# CC2652P_STICK_v1_1.net
KiCad netlist of a schematic drawn in EAGLE
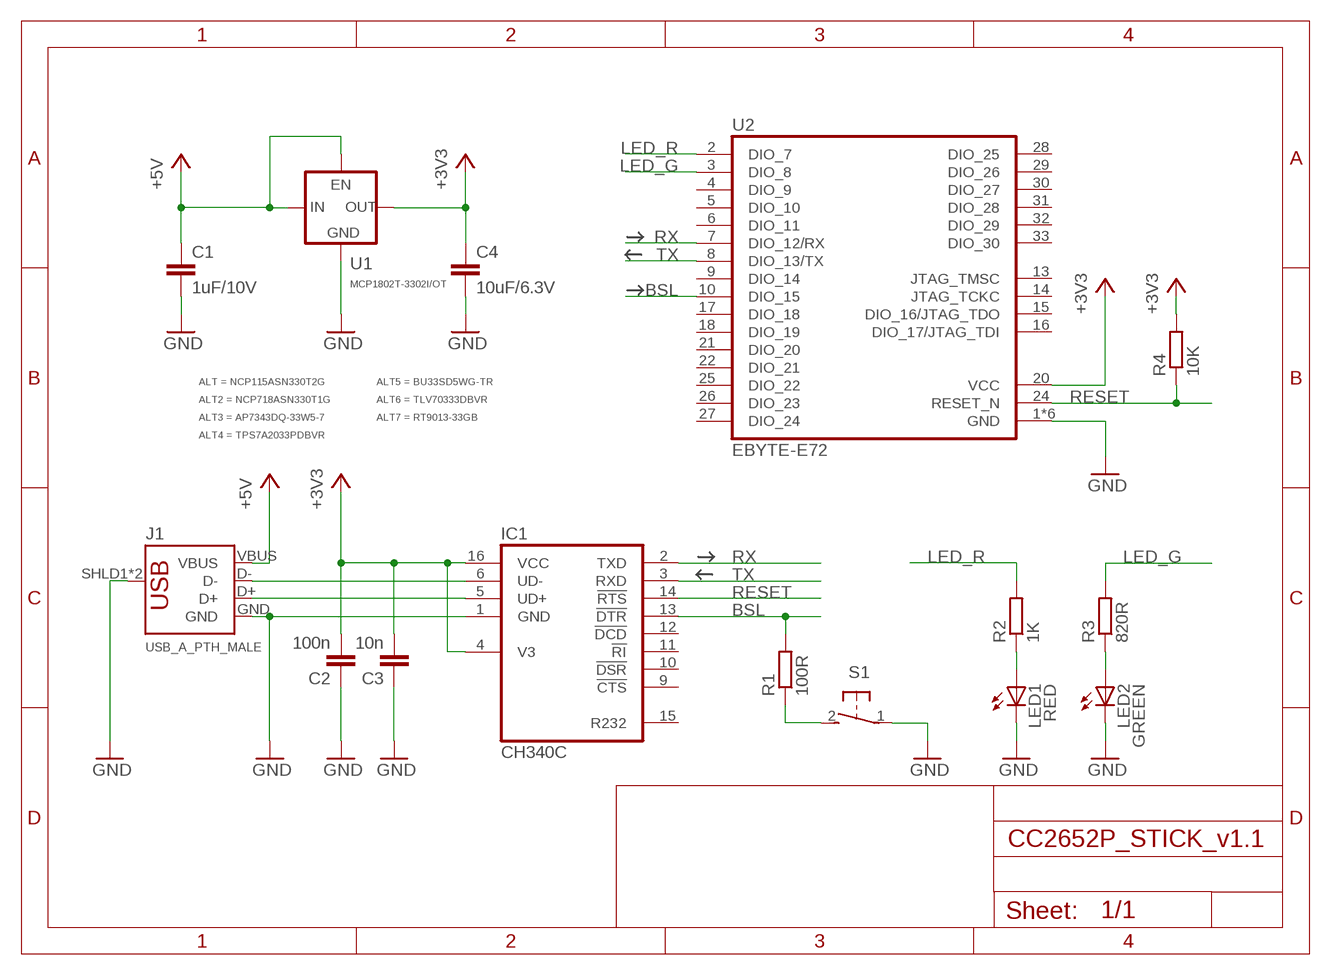
[diagram p0: schematic, sheet 1]

(export (version "E")
  (design (tool "Eeschema 10.0.6"))
  (components
    (comp (ref "C1")
      (value "1uF/10V")
      (footprint "eagle-import:C0805")
      (libsource (lib "eagle-import") (part "C-EUC0805"))
    )
    (comp (ref "C2")
      (value "100n")
      (footprint "eagle-import:C0805")
      (libsource (lib "eagle-import") (part "C-EUC0805"))
    )
    (comp (ref "C3")
      (value "10n")
      (footprint "eagle-import:C0805")
      (libsource (lib "eagle-import") (part "C-EUC0805"))
    )
    (comp (ref "C4")
      (value "10uF/6.3V")
      (footprint "eagle-import:C0805")
      (libsource (lib "eagle-import") (part "C-EUC0805"))
    )
    (comp (ref "IC1")
      (value "CH340C")
      (footprint "eagle-import:SO16")
      (libsource (lib "eagle-import") (part "CH340C"))
    )
    (comp (ref "J1")
      (value "USB_A_PTH_MALE")
      (footprint "eagle-import:USB-A-H")
      (libsource (lib "eagle-import") (part "USB_A_PTH_MALE"))
    )
    (comp (ref "LED1")
      (value "RED")
      (footprint "eagle-import:LED0603")
      (libsource (lib "eagle-import") (part "LED0603"))
    )
    (comp (ref "LED2")
      (value "GREEN")
      (footprint "eagle-import:LED0603")
      (libsource (lib "eagle-import") (part "LED0603"))
    )
    (comp (ref "R1")
      (value "100R")
      (footprint "eagle-import:R0805")
      (libsource (lib "eagle-import") (part "R-EU_R0805"))
    )
    (comp (ref "R2")
      (value "1K")
      (footprint "eagle-import:R0805")
      (libsource (lib "eagle-import") (part "R-EU_R0805"))
    )
    (comp (ref "R3")
      (value "820R")
      (footprint "eagle-import:R0805")
      (libsource (lib "eagle-import") (part "R-EU_R0805"))
    )
    (comp (ref "R4")
      (value "10K")
      (footprint "eagle-import:R0805")
      (libsource (lib "eagle-import") (part "R-EU_R0805"))
    )
    (comp (ref "S1")
      (value "DTSM-3")
      (footprint "eagle-import:DTSM-3")
      (libsource (lib "eagle-import") (part "DTSM-3"))
    )
    (comp (ref "U1")
      (value "MCP1802T-3302I/OT")
      (footprint "eagle-import:SOT23-5")
      (fields
        (field (name "ALT") "NCP115ASN330T2G")
        (field (name "ALT2") "NCP718ASN330T1G")
        (field (name "ALT3") "AP7343DQ-33W5-7")
        (field (name "ALT4") "TPS7A2033PDBVR")
        (field (name "ALT5") "BU33SD5WG-TR")
        (field (name "ALT6") "TLV70333DBVR")
        (field (name "ALT7") "RT9013-33GB")
      )
      (libsource (lib "eagle-import") (part "TLV700DD33"))
    )
    (comp (ref "U2")
      (value "EBYTE-E72")
      (footprint "eagle-import:EBYTE-E72")
      (libsource (lib "eagle-import") (part "EBYTE-E72"))
    )
  )
  (nets
    (net (code "1") (name "+3V3") (class "Default")
      (node (ref "C2") (pin "2") (pinfunction "2_2") (pintype "passive"))
      (node (ref "C3") (pin "2") (pinfunction "2_2") (pintype "passive"))
      (node (ref "C4") (pin "1") (pinfunction "1_1") (pintype "passive"))
      (node (ref "IC1") (pin "16") (pinfunction "VCC_16") (pintype "power_in"))
      (node (ref "IC1") (pin "4") (pinfunction "V3_4") (pintype "passive"))
      (node (ref "R4") (pin "2") (pinfunction "2_2") (pintype "passive"))
      (node (ref "U1") (pin "5") (pinfunction "VOUT_5") (pintype "power_in"))
      (node (ref "U2") (pin "20") (pinfunction "VCC_20") (pintype "power_in"))
    )
    (net (code "2") (name "+5V") (class "Default")
      (node (ref "C1") (pin "1") (pinfunction "1_1") (pintype "passive"))
      (node (ref "J1") (pin "VBUS") (pinfunction "VBUS_VBUS") (pintype "power_in"))
      (node (ref "U1") (pin "1") (pinfunction "VIN_1") (pintype "power_in"))
      (node (ref "U1") (pin "3") (pinfunction "EN_3") (pintype "input"))
    )
    (net (code "3") (name "/BSL") (class "Default")
      (node (ref "IC1") (pin "13") (pinfunction "~{DTR}_13") (pintype "bidirectional"))
      (node (ref "R1") (pin "2") (pinfunction "2_2") (pintype "passive"))
      (node (ref "U2") (pin "10") (pinfunction "DIO_15_10") (pintype "bidirectional"))
    )
    (net (code "4") (name "/LED_G") (class "Default")
      (node (ref "R3") (pin "2") (pinfunction "2_2") (pintype "passive"))
      (node (ref "U2") (pin "3") (pinfunction "DIO_8_3") (pintype "bidirectional"))
    )
    (net (code "5") (name "/LED_R") (class "Default")
      (node (ref "R2") (pin "2") (pinfunction "2_2") (pintype "passive"))
      (node (ref "U2") (pin "2") (pinfunction "DIO_7_2") (pintype "bidirectional"))
    )
    (net (code "6") (name "/RESET") (class "Default")
      (node (ref "IC1") (pin "14") (pinfunction "~{RTS}_14") (pintype "bidirectional"))
      (node (ref "R4") (pin "1") (pinfunction "1_1") (pintype "passive"))
      (node (ref "U2") (pin "24") (pinfunction "RESET_N_24") (pintype "input"))
    )
    (net (code "7") (name "/RX") (class "Default")
      (node (ref "IC1") (pin "2") (pinfunction "TXD_2") (pintype "output"))
      (node (ref "U2") (pin "7") (pinfunction "DIO_12/RX_7") (pintype "bidirectional"))
    )
    (net (code "8") (name "/TX") (class "Default")
      (node (ref "IC1") (pin "3") (pinfunction "RXD_3") (pintype "input"))
      (node (ref "U2") (pin "8") (pinfunction "DIO_13/TX_8") (pintype "bidirectional"))
    )
    (net (code "9") (name "GND") (class "Default")
      (node (ref "C1") (pin "2") (pinfunction "2_2") (pintype "passive"))
      (node (ref "C2") (pin "1") (pinfunction "1_1") (pintype "passive"))
      (node (ref "C3") (pin "1") (pinfunction "1_1") (pintype "passive"))
      (node (ref "C4") (pin "2") (pinfunction "2_2") (pintype "passive"))
      (node (ref "IC1") (pin "1") (pinfunction "GND_1") (pintype "power_in"))
      (node (ref "J1") (pin "GND") (pinfunction "GND_GND") (pintype "power_in"))
      (node (ref "J1") (pin "SHLD1") (pinfunction "SHIELD_SHLD1") (pintype "bidirectional"))
      (node (ref "J1") (pin "SHLD2") (pinfunction "SHIELD_SHLD2") (pintype "bidirectional"))
      (node (ref "LED1") (pin "C") (pinfunction "C_C") (pintype "passive"))
      (node (ref "LED2") (pin "C") (pinfunction "C_C") (pintype "passive"))
      (node (ref "S1") (pin "1") (pinfunction "1_1") (pintype "passive"))
      (node (ref "U1") (pin "2") (pinfunction "GND_2") (pintype "power_in"))
      (node (ref "U2") (pin "1") (pinfunction "GND_1") (pintype "power_in"))
      (node (ref "U2") (pin "11") (pinfunction "GND_11") (pintype "power_in"))
      (node (ref "U2") (pin "12") (pinfunction "GND_12") (pintype "power_in"))
      (node (ref "U2") (pin "19") (pinfunction "GND_19") (pintype "power_in"))
      (node (ref "U2") (pin "23") (pinfunction "GND_23") (pintype "power_in"))
      (node (ref "U2") (pin "34") (pinfunction "GND_34") (pintype "power_in"))
    )
    (net (code "10") (name "Net-(IC1-UD+)") (class "Default")
      (node (ref "IC1") (pin "5") (pinfunction "UD+_5") (pintype "bidirectional"))
      (node (ref "J1") (pin "D+") (pinfunction "D+_D+") (pintype "bidirectional"))
    )
    (net (code "11") (name "Net-(IC1-UD-)") (class "Default")
      (node (ref "IC1") (pin "6") (pinfunction "UD-_6") (pintype "bidirectional"))
      (node (ref "J1") (pin "D-") (pinfunction "D-_D-") (pintype "bidirectional"))
    )
    (net (code "12") (name "Net-(LED1-PadA)") (class "Default")
      (node (ref "LED1") (pin "A") (pinfunction "A_A") (pintype "passive"))
      (node (ref "R2") (pin "1") (pinfunction "1_1") (pintype "passive"))
    )
    (net (code "13") (name "Net-(LED2-PadA)") (class "Default")
      (node (ref "LED2") (pin "A") (pinfunction "A_A") (pintype "passive"))
      (node (ref "R3") (pin "1") (pinfunction "1_1") (pintype "passive"))
    )
    (net (code "14") (name "Net-(R1-Pad1)") (class "Default")
      (node (ref "R1") (pin "1") (pinfunction "1_1") (pintype "passive"))
      (node (ref "S1") (pin "2") (pinfunction "2_2") (pintype "passive"))
    )
    (net (code "15") (name "unconnected-(IC1-R232-Pad15)") (class "Default")
      (node (ref "IC1") (pin "15") (pinfunction "R232_15") (pintype "bidirectional"))
    )
    (net (code "16") (name "unconnected-(IC1-~{CTS}-Pad9)") (class "Default")
      (node (ref "IC1") (pin "9") (pinfunction "~{CTS}_9") (pintype "bidirectional"))
    )
    (net (code "17") (name "unconnected-(IC1-~{DCD}-Pad12)") (class "Default")
      (node (ref "IC1") (pin "12") (pinfunction "~{DCD}_12") (pintype "bidirectional"))
    )
    (net (code "18") (name "unconnected-(IC1-~{DSR}-Pad10)") (class "Default")
      (node (ref "IC1") (pin "10") (pinfunction "~{DSR}_10") (pintype "bidirectional"))
    )
    (net (code "19") (name "unconnected-(IC1-~{RI}-Pad11)") (class "Default")
      (node (ref "IC1") (pin "11") (pinfunction "~{RI}_11") (pintype "bidirectional"))
    )
    (net (code "20") (name "unconnected-(U2-DIO_9-Pad4)") (class "Default")
      (node (ref "U2") (pin "4") (pinfunction "DIO_9_4") (pintype "bidirectional"))
    )
    (net (code "21") (name "unconnected-(U2-DIO_10-Pad5)") (class "Default")
      (node (ref "U2") (pin "5") (pinfunction "DIO_10_5") (pintype "bidirectional"))
    )
    (net (code "22") (name "unconnected-(U2-DIO_11-Pad6)") (class "Default")
      (node (ref "U2") (pin "6") (pinfunction "DIO_11_6") (pintype "bidirectional"))
    )
    (net (code "23") (name "unconnected-(U2-DIO_14-Pad9)") (class "Default")
      (node (ref "U2") (pin "9") (pinfunction "DIO_14_9") (pintype "bidirectional"))
    )
    (net (code "24") (name "unconnected-(U2-DIO_16{slash}JTAG_TDO-Pad15)") (class "Default")
      (node (ref "U2") (pin "15") (pinfunction "DIO_16/JTAG_TDO_15") (pintype "bidirectional"))
    )
    (net (code "25") (name "unconnected-(U2-DIO_17{slash}JTAG_TDI-Pad16)") (class "Default")
      (node (ref "U2") (pin "16") (pinfunction "DIO_17/JTAG_TDI_16") (pintype "bidirectional"))
    )
    (net (code "26") (name "unconnected-(U2-DIO_18-Pad17)") (class "Default")
      (node (ref "U2") (pin "17") (pinfunction "DIO_18_17") (pintype "bidirectional"))
    )
    (net (code "27") (name "unconnected-(U2-DIO_19-Pad18)") (class "Default")
      (node (ref "U2") (pin "18") (pinfunction "DIO_19_18") (pintype "bidirectional"))
    )
    (net (code "28") (name "unconnected-(U2-DIO_20-Pad21)") (class "Default")
      (node (ref "U2") (pin "21") (pinfunction "DIO_20_21") (pintype "bidirectional"))
    )
    (net (code "29") (name "unconnected-(U2-DIO_21-Pad22)") (class "Default")
      (node (ref "U2") (pin "22") (pinfunction "DIO_21_22") (pintype "bidirectional"))
    )
    (net (code "30") (name "unconnected-(U2-DIO_22-Pad25)") (class "Default")
      (node (ref "U2") (pin "25") (pinfunction "DIO_22_25") (pintype "bidirectional"))
    )
    (net (code "31") (name "unconnected-(U2-DIO_23-Pad26)") (class "Default")
      (node (ref "U2") (pin "26") (pinfunction "DIO_23_26") (pintype "bidirectional"))
    )
    (net (code "32") (name "unconnected-(U2-DIO_24-Pad27)") (class "Default")
      (node (ref "U2") (pin "27") (pinfunction "DIO_24_27") (pintype "bidirectional"))
    )
    (net (code "33") (name "unconnected-(U2-DIO_25-Pad28)") (class "Default")
      (node (ref "U2") (pin "28") (pinfunction "DIO_25_28") (pintype "bidirectional"))
    )
    (net (code "34") (name "unconnected-(U2-DIO_26-Pad29)") (class "Default")
      (node (ref "U2") (pin "29") (pinfunction "DIO_26_29") (pintype "bidirectional"))
    )
    (net (code "35") (name "unconnected-(U2-DIO_27-Pad30)") (class "Default")
      (node (ref "U2") (pin "30") (pinfunction "DIO_27_30") (pintype "bidirectional"))
    )
    (net (code "36") (name "unconnected-(U2-DIO_28-Pad31)") (class "Default")
      (node (ref "U2") (pin "31") (pinfunction "DIO_28_31") (pintype "bidirectional"))
    )
    (net (code "37") (name "unconnected-(U2-DIO_29-Pad32)") (class "Default")
      (node (ref "U2") (pin "32") (pinfunction "DIO_29_32") (pintype "bidirectional"))
    )
    (net (code "38") (name "unconnected-(U2-DIO_30-Pad33)") (class "Default")
      (node (ref "U2") (pin "33") (pinfunction "DIO_30_33") (pintype "bidirectional"))
    )
    (net (code "39") (name "unconnected-(U2-JTAG_TCKC-Pad14)") (class "Default")
      (node (ref "U2") (pin "14") (pinfunction "JTAG_TCKC_14") (pintype "bidirectional"))
    )
    (net (code "40") (name "unconnected-(U2-JTAG_TMSC-Pad13)") (class "Default")
      (node (ref "U2") (pin "13") (pinfunction "JTAG_TMSC_13") (pintype "bidirectional"))
    )
  )
)
